# POE_RS-485.net
KiCad netlist of a schematic drawn in EAGLE
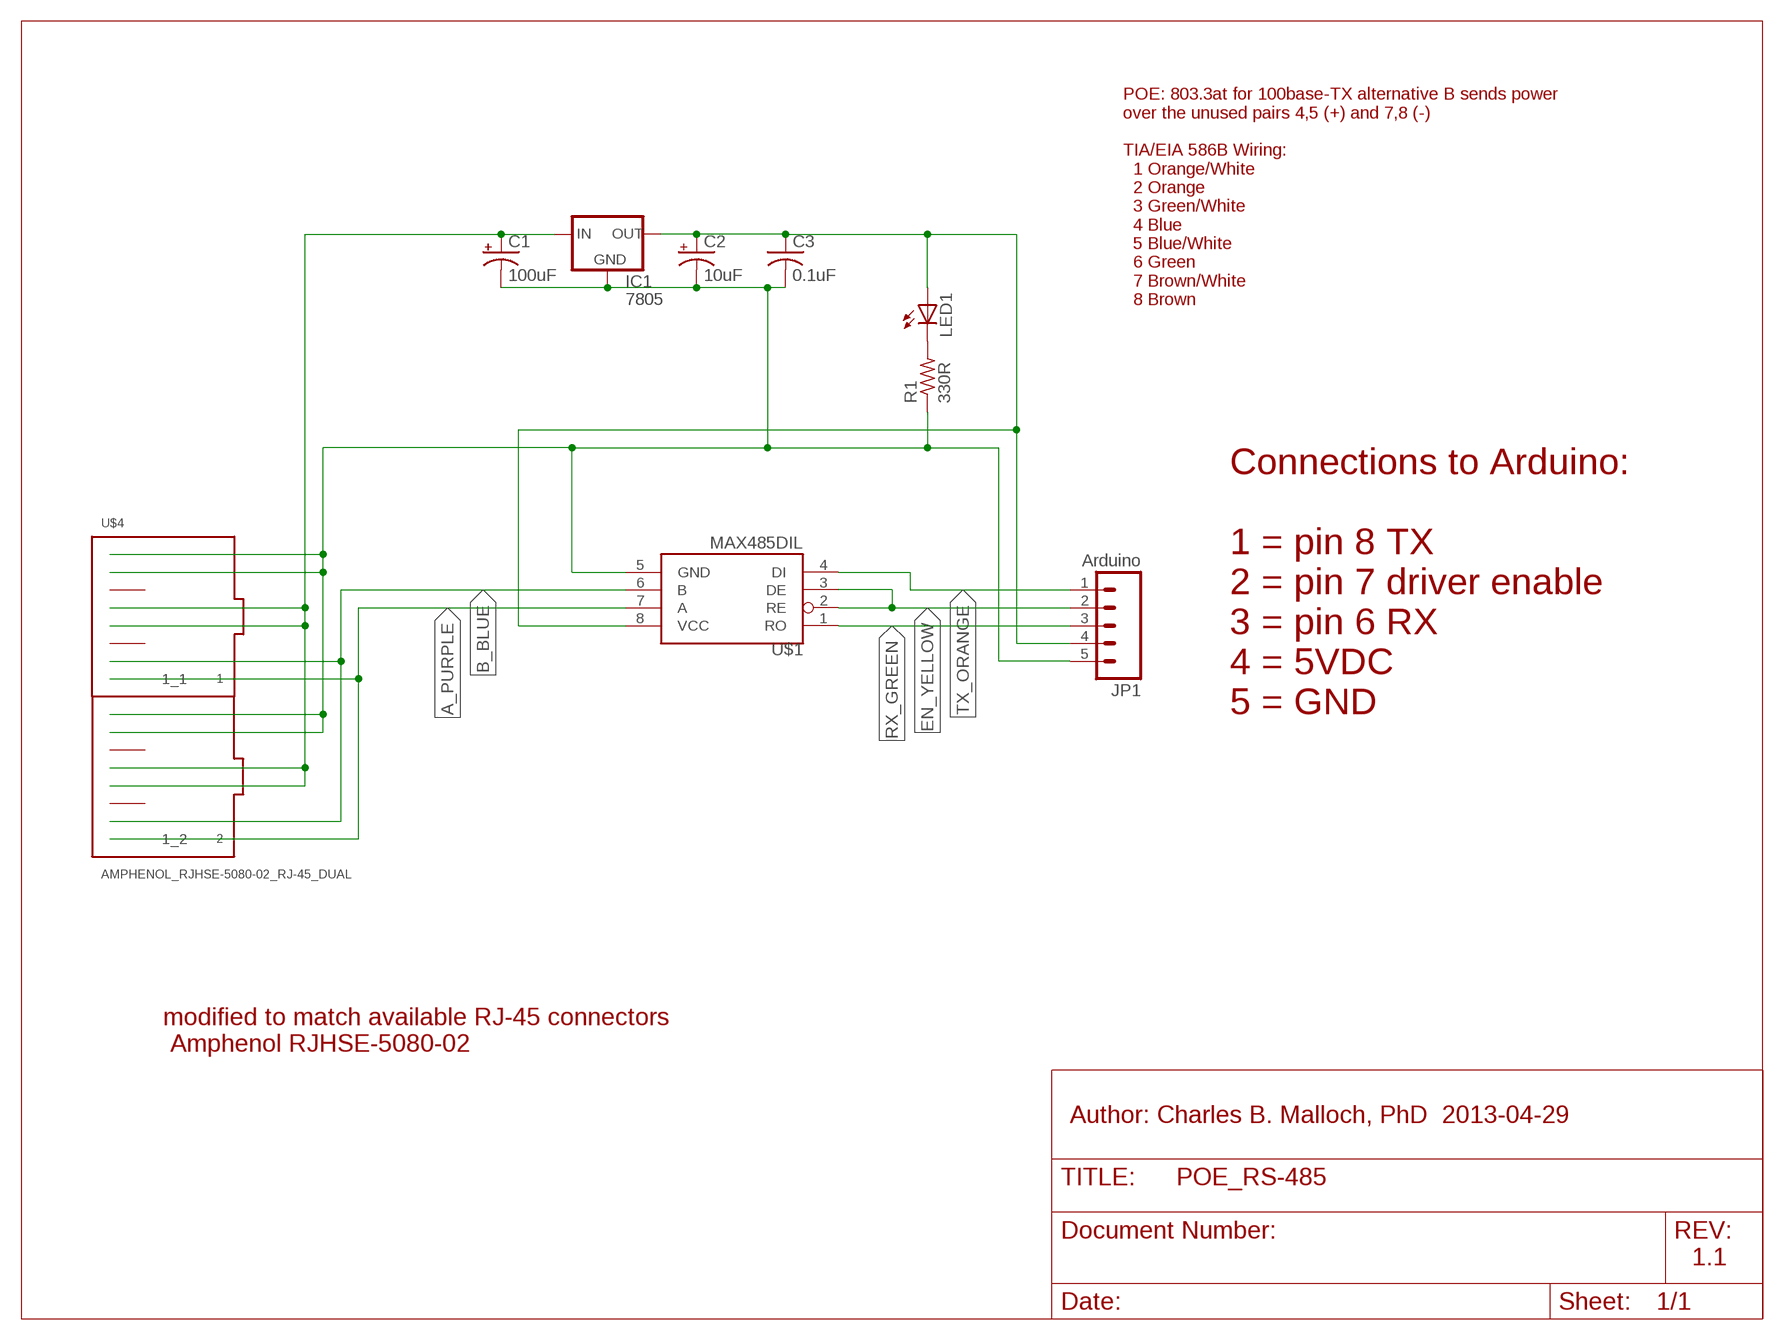
[diagram p0: schematic, sheet 1]

(export (version "E")
  (design (tool "Eeschema 10.0.6"))
  (components
    (comp (ref "C1")
      (value "100uF")
      (footprint "eagle-import:TT2D7")
      (libsource (lib "eagle-import") (part "CPOL-USTT2D7"))
    )
    (comp (ref "C2")
      (value "10uF")
      (footprint "eagle-import:E1,8-4")
      (libsource (lib "eagle-import") (part "CPOL-USE1.8-4"))
    )
    (comp (ref "C3")
      (value "0.1uF")
      (footprint "eagle-import:C025-025X050")
      (libsource (lib "eagle-import") (part "C-US025-025X050"))
    )
    (comp (ref "IC1")
      (value "7805")
      (footprint "eagle-import:TO-220-ALT")
      (libsource (lib "eagle-import") (part "V_REG_78XX-TO-220"))
    )
    (comp (ref "JP1")
      (value "Arduino")
      (footprint "eagle-import:1X05_LOCK_LONGPADS")
      (libsource (lib "eagle-import") (part "M05LOCK_LONGPADS"))
    )
    (comp (ref "LED1")
      (value "LED3MM")
      (footprint "eagle-import:LED3MM")
      (libsource (lib "eagle-import") (part "LED3MM"))
    )
    (comp (ref "R1")
      (value "330R")
      (footprint "eagle-import:0204_7")
      (libsource (lib "eagle-import") (part "R-US_0204/7"))
    )
    (comp (ref "U$1")
      (value "MAX485DIL")
      (footprint "eagle-import:DIL08")
      (libsource (lib "eagle-import") (part "MAX485DIL"))
    )
    (comp (ref "U$4")
      (value "AMPHENOL_RJHSE-5080-02_RJ-45_DUAL")
      (footprint "eagle-import:AMPHENOL_RJHSE-5080-02")
      (libsource (lib "eagle-import") (part "AMPHENOL_RJHSE-5080-02_RJ-45_DUAL"))
    )
  )
  (nets
    (net (code "1") (name "A_PURPLE") (class "Default")
      (node (ref "U$1") (pin "7") (pinfunction "A_7") (pintype "bidirectional"))
      (node (ref "U$4") (pin "TX_D1+_2") (pinfunction "1_2_TX_D1+_2") (pintype "bidirectional"))
      (node (ref "U$4") (pin "TX_DI+_1") (pinfunction "1_1_TX_DI+_1") (pintype "bidirectional"))
    )
    (net (code "2") (name "B_BLUE") (class "Default")
      (node (ref "U$1") (pin "6") (pinfunction "B_6") (pintype "bidirectional"))
      (node (ref "U$4") (pin "TX_D1-_2") (pinfunction "2_2_TX_D1-_2") (pintype "bidirectional"))
      (node (ref "U$4") (pin "TX_DI-_1") (pinfunction "2_1_TX_DI-_1") (pintype "bidirectional"))
    )
    (net (code "3") (name "EN_YELLOW") (class "Default")
      (node (ref "JP1") (pin "2") (pinfunction "2_2") (pintype "passive"))
      (node (ref "U$1") (pin "2") (pinfunction "RE_2") (pintype "bidirectional"))
      (node (ref "U$1") (pin "3") (pinfunction "DE_3") (pintype "bidirectional"))
    )
    (net (code "4") (name "Net-(LED1-C)") (class "Default")
      (node (ref "LED1") (pin "K") (pinfunction "C_K") (pintype "passive"))
      (node (ref "R1") (pin "2") (pinfunction "2_2") (pintype "passive"))
    )
    (net (code "5") (name "Net-(U$1-GND)") (class "Default")
      (node (ref "C1") (pin "-") (pinfunction "-_-") (pintype "passive"))
      (node (ref "C2") (pin "-") (pinfunction "-_-") (pintype "passive"))
      (node (ref "C3") (pin "2") (pinfunction "2_2") (pintype "passive"))
      (node (ref "IC1") (pin "GND") (pinfunction "GND_GND") (pintype "input"))
      (node (ref "JP1") (pin "5") (pinfunction "5_5") (pintype "passive"))
      (node (ref "R1") (pin "1") (pinfunction "1_1") (pintype "passive"))
      (node (ref "U$1") (pin "5") (pinfunction "GND_5") (pintype "bidirectional"))
      (node (ref "U$4") (pin "POE-_1_1") (pinfunction "7_1_POE-_1_1") (pintype "bidirectional"))
      (node (ref "U$4") (pin "POE-_1_2") (pinfunction "7_2_POE-_1_2") (pintype "bidirectional"))
      (node (ref "U$4") (pin "POE-_2_1") (pinfunction "8_1_POE-_2_1") (pintype "bidirectional"))
      (node (ref "U$4") (pin "POE-_2_2") (pinfunction "8_2_POE-_2_2") (pintype "bidirectional"))
    )
    (net (code "6") (name "Net-(U$1-VCC)") (class "Default")
      (node (ref "C2") (pin "+") (pinfunction "+_+") (pintype "passive"))
      (node (ref "C3") (pin "1") (pinfunction "1_1") (pintype "passive"))
      (node (ref "IC1") (pin "OUT") (pinfunction "OUT_OUT") (pintype "output"))
      (node (ref "JP1") (pin "4") (pinfunction "4_4") (pintype "passive"))
      (node (ref "LED1") (pin "A") (pinfunction "A_A") (pintype "passive"))
      (node (ref "U$1") (pin "8") (pinfunction "VCC_8") (pintype "bidirectional"))
    )
    (net (code "7") (name "Net-(U$4-4_1)") (class "Default")
      (node (ref "C1") (pin "+") (pinfunction "+_+") (pintype "passive"))
      (node (ref "IC1") (pin "IN") (pinfunction "IN_IN") (pintype "input"))
      (node (ref "U$4") (pin "POE+_1_1") (pinfunction "4_1_POE+_1_1") (pintype "bidirectional"))
      (node (ref "U$4") (pin "POE+_1_2") (pinfunction "4_2_POE+_1_2") (pintype "bidirectional"))
      (node (ref "U$4") (pin "POE+_2_1") (pinfunction "5_1_POE+_2_1") (pintype "bidirectional"))
      (node (ref "U$4") (pin "POE+_2_2") (pinfunction "5_2_POE+_2_2") (pintype "bidirectional"))
    )
    (net (code "8") (name "RX_GREEN") (class "Default")
      (node (ref "JP1") (pin "3") (pinfunction "3_3") (pintype "passive"))
      (node (ref "U$1") (pin "1") (pinfunction "RO_1") (pintype "bidirectional"))
    )
    (net (code "9") (name "TX_ORANGE") (class "Default")
      (node (ref "JP1") (pin "1") (pinfunction "1_1") (pintype "passive"))
      (node (ref "U$1") (pin "4") (pinfunction "DI_4") (pintype "bidirectional"))
    )
    (net (code "10") (name "unconnected-(U$4-3_1-PadRX_D2+_1)") (class "Default")
      (node (ref "U$4") (pin "RX_D2+_1") (pinfunction "3_1_RX_D2+_1") (pintype "bidirectional"))
    )
    (net (code "11") (name "unconnected-(U$4-3_2-PadRX_D2+_2)") (class "Default")
      (node (ref "U$4") (pin "RX_D2+_2") (pinfunction "3_2_RX_D2+_2") (pintype "bidirectional"))
    )
    (net (code "12") (name "unconnected-(U$4-6_1-PadRX_D2-_1)") (class "Default")
      (node (ref "U$4") (pin "RX_D2-_1") (pinfunction "6_1_RX_D2-_1") (pintype "bidirectional"))
    )
    (net (code "13") (name "unconnected-(U$4-6_2-PadRX_D2-_2)") (class "Default")
      (node (ref "U$4") (pin "RX_D2-_2") (pinfunction "6_2_RX_D2-_2") (pintype "bidirectional"))
    )
  )
)
